# -LM3670.net
KiCad netlist of a schematic drawn in Altium Designer
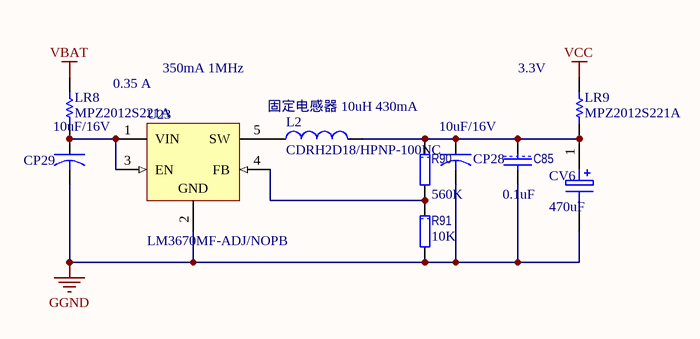
[diagram p0: -LM3670_电源.SchDoc]

(export (version "E")
  (design (tool "Eeschema 10.0.6"))
  (components
    (comp (ref "C85")
      (value "0.1uF")
      (footprint "1608[0603]C")
      (description "多层陶瓷电容器MLCC - SMD/SMT 0603 0.1uF 50volts X7R 10%")
      (fields (field (name "MANUFACTURER") "TDK") (field (name "MANUFACTURER PART NUMBER") "C1608X7R1H104K"))
      (libsource (lib "*") (part "CAP"))
    )
    (comp (ref "CP28")
      (value "10uF/16V")
      (footprint "3216[1206]CB")
      (description "钽质电容器-固体SMD 16volts 10uF 10%")
      (fields (field (name "MANUFACTURER") "AVX") (field (name "MANUFACTURER PART NUMBER") "TAJA106K016RNJ"))
      (libsource (lib "*") (part "CAPACITOR"))
    )
    (comp (ref "CP29")
      (value "10uF/16V")
      (footprint "3216[1206]CB")
      (description "钽质电容器-固体SMD 16volts 10uF 10%")
      (fields (field (name "MANUFACTURER") "AVX") (field (name "MANUFACTURER PART NUMBER") "TAJA106K016RNJ"))
      (libsource (lib "*") (part "CAPACITOR"))
    )
    (comp (ref "CV6")
      (value "470uF")
      (footprint "CAPPR5-10x20/H1.1")
      (description "插针 铝质电解电容器 - 带引线 470UF 35V ELECT FM RADIAL")
      (fields
        (field (name "MANUFACTURER") "Panasonic Electronic Components")
        (field (name "MANUFACTURER PART NUMBER") "EEU-FM1V471")
      )
      (libsource (lib "*") (part "ELECTRO1"))
    )
    (comp (ref "L2")
      (value "CDRH2D18/HPNP-100NC")
      (footprint "INDP3232")
      (description "固定电感器 10uH 430mA")
      (fields (field (name "MANUFACTURER") "Sumida") (field (name "DESCRIPTION 1") "固定电感器 10uH 430mA"))
      (libsource (lib "Miscellaneous Devices") (part "Inductor"))
    )
    (comp (ref "LR8")
      (value "MPZ2012S221A")
      (footprint "2012[0805]")
      (description "电磁干扰滤波珠子、扼流圈和阵列 Ferrite Chip Beads")
      (fields (field (name "MANUFACTURER") "TDK"))
      (libsource (lib "Miscellaneous Devices") (part "Res Semi"))
    )
    (comp (ref "LR9")
      (value "MPZ2012S221A")
      (footprint "2012[0805]")
      (description "电磁干扰滤波珠子、扼流圈和阵列 Ferrite Chip Beads")
      (fields (field (name "MANUFACTURER") "TDK"))
      (libsource (lib "Miscellaneous Devices") (part "Res Semi"))
    )
    (comp (ref "R90")
      (value "560K")
      (footprint "2012[0805]R")
      (description "薄膜电阻器 - SMD 560K  OHM  .1% 25PPM")
      (fields
        (field (name "MANUFACTURER") "Vishay")
        (field (name "MANUFACTURER PART NUMBER") "TNPW0805560KBEEN")
      )
      (libsource (lib "10K 1%") (part "RES"))
    )
    (comp (ref "R91")
      (value "10K")
      (footprint "1608[0603]R")
      (description "厚膜电阻器 - SMD 1/10watt 10Kohms 1%")
      (fields
        (field (name "MANUFACTURER") "Vishay / Dale")
        (field (name "MANUFACTURER PART NUMBER") "CRCW060310K0FKEA")
      )
      (libsource (lib "10K 1%") (part "RES"))
    )
    (comp (ref "U23")
      (value "LM3670MF-ADJ/NOPB")
      (footprint "SOT23-5BN")
      (description "DC/DC 开关控制器 Mini SD DC-DC Cnvtr")
      (fields (field (name "MANUFACTURER") "Texas Instruments") (field (name "ÊÄ³ÖΜÇÁ÷") "0.35 A"))
      (libsource (lib "NSC Switcher") (part "LM3670MF-3.3/NOPB"))
    )
  )
  (nets
    (net (code "1") (name "GGND") (class "Default")
      (node (ref "C85") (pin "2") (pinfunction "2_2") (pintype "passive"))
      (node (ref "CP28") (pin "2") (pinfunction "2_2") (pintype "passive"))
      (node (ref "CP29") (pin "2") (pinfunction "2_2") (pintype "passive"))
      (node (ref "CV6") (pin "2") (pinfunction "2_2") (pintype "passive"))
      (node (ref "R91") (pin "2") (pinfunction "2_2") (pintype "passive"))
      (node (ref "U23") (pin "2") (pinfunction "GND_2") (pintype "power_in"))
    )
    (net (code "2") (name "Net-(C85-Pad1)") (class "Default")
      (node (ref "C85") (pin "1") (pinfunction "1_1") (pintype "passive"))
      (node (ref "CP28") (pin "1") (pinfunction "1_1") (pintype "passive"))
      (node (ref "CV6") (pin "1") (pinfunction "1_1") (pintype "passive"))
      (node (ref "L2") (pin "2") (pinfunction "2_2") (pintype "passive"))
      (node (ref "LR9") (pin "1") (pinfunction "1_1") (pintype "passive"))
      (node (ref "R90") (pin "1") (pinfunction "1_1") (pintype "passive"))
    )
    (net (code "3") (name "Net-(U23-EN)") (class "Default")
      (node (ref "CP29") (pin "1") (pinfunction "1_1") (pintype "passive"))
      (node (ref "LR8") (pin "1") (pinfunction "1_1") (pintype "passive"))
      (node (ref "U23") (pin "1") (pinfunction "VIN_1") (pintype "power_in"))
      (node (ref "U23") (pin "3") (pinfunction "EN_3") (pintype "input"))
    )
    (net (code "4") (name "Net-(U23-FB)") (class "Default")
      (node (ref "R90") (pin "2") (pinfunction "2_2") (pintype "passive"))
      (node (ref "R91") (pin "1") (pinfunction "1_1") (pintype "passive"))
      (node (ref "U23") (pin "4") (pinfunction "FB_4") (pintype "input"))
    )
    (net (code "5") (name "Net-(U23-SW)") (class "Default")
      (node (ref "L2") (pin "1") (pinfunction "1_1") (pintype "passive"))
      (node (ref "U23") (pin "5") (pinfunction "SW_5") (pintype "power_in"))
    )
    (net (code "6") (name "VBAT") (class "Default")
      (node (ref "LR8") (pin "2") (pinfunction "2_2") (pintype "passive"))
    )
    (net (code "7") (name "VCC") (class "Default")
      (node (ref "LR9") (pin "2") (pinfunction "2_2") (pintype "passive"))
    )
  )
)
